# 4bitDecoder.net
KiCad netlist of a schematic drawn in Altium Designer
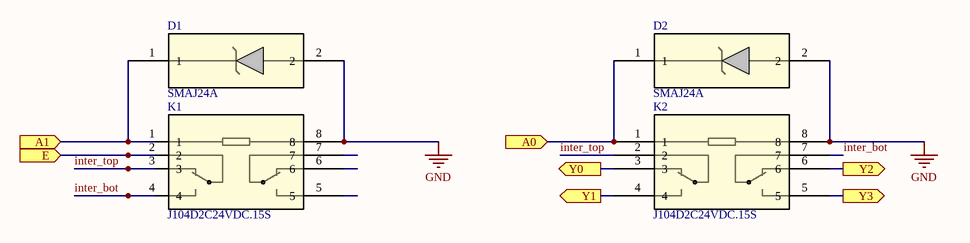
[diagram p0: 4bitDecoder.SchDoc]

(export (version "E")
  (design (tool "Eeschema 10.0.6"))
  (components
    (comp (ref "D1")
      (value "SMAJ24A")
      (footprint "DI SMAJ24A")
      (description "SMAJ Series 400 W 24 V Uni-Directional Surface Mount TVS Diode - DO-214AC")
      (fields (field (name "MANUFACTURER") "Littelfuse"))
      (libsource (lib "Schlib1") (part "DI SMAJ24A"))
    )
    (comp (ref "D2")
      (value "SMAJ24A")
      (footprint "DI SMAJ24A")
      (description "SMAJ Series 400 W 24 V Uni-Directional Surface Mount TVS Diode - DO-214AC")
      (fields (field (name "MANUFACTURER") "Littelfuse"))
      (libsource (lib "Schlib1") (part "DI SMAJ24A"))
    )
    (comp (ref "K1")
      (value "J104D2C24VDC.15S")
      (footprint "Relay J104D2C24VDC.15S")
      (description "Relay Ul Gen Purp DPDT 2C 24VDC")
      (fields (field (name "MANUFACTURER") "CIT Relay & Switch"))
      (libsource (lib "Schlib1") (part "Relay J104D2C24VDC.15S"))
    )
    (comp (ref "K2")
      (value "J104D2C24VDC.15S")
      (footprint "Relay J104D2C24VDC.15S")
      (description "Relay Ul Gen Purp DPDT 2C 24VDC")
      (fields (field (name "MANUFACTURER") "CIT Relay & Switch"))
      (libsource (lib "Schlib1") (part "Relay J104D2C24VDC.15S"))
    )
  )
  (nets
    (net (code "1") (name "/A0") (class "Default")
      (node (ref "D2") (pin "1") (pinfunction "1_1") (pintype "passive"))
      (node (ref "K2") (pin "1") (pinfunction "1_1") (pintype "passive"))
    )
    (net (code "2") (name "/A1") (class "Default")
      (node (ref "D1") (pin "1") (pinfunction "1_1") (pintype "passive"))
      (node (ref "K1") (pin "1") (pinfunction "1_1") (pintype "passive"))
    )
    (net (code "3") (name "/E") (class "Default")
      (node (ref "K1") (pin "2") (pinfunction "2_2") (pintype "passive"))
    )
    (net (code "4") (name "/Y0") (class "Default")
      (node (ref "K2") (pin "3") (pinfunction "3_3") (pintype "passive"))
    )
    (net (code "5") (name "/Y1") (class "Default")
      (node (ref "K2") (pin "4") (pinfunction "4_4") (pintype "passive"))
    )
    (net (code "6") (name "/Y2") (class "Default")
      (node (ref "K2") (pin "6") (pinfunction "6_6") (pintype "passive"))
    )
    (net (code "7") (name "/Y3") (class "Default")
      (node (ref "K2") (pin "5") (pinfunction "5_5") (pintype "passive"))
    )
    (net (code "8") (name "/inter_bot") (class "Default")
      (node (ref "K1") (pin "4") (pinfunction "4_4") (pintype "passive"))
      (node (ref "K2") (pin "7") (pinfunction "7_7") (pintype "passive"))
    )
    (net (code "9") (name "/inter_top") (class "Default")
      (node (ref "K1") (pin "3") (pinfunction "3_3") (pintype "passive"))
      (node (ref "K2") (pin "2") (pinfunction "2_2") (pintype "passive"))
    )
    (net (code "10") (name "GND") (class "Default")
      (node (ref "D1") (pin "2") (pinfunction "2_2") (pintype "passive"))
      (node (ref "D2") (pin "2") (pinfunction "2_2") (pintype "passive"))
      (node (ref "K1") (pin "8") (pinfunction "8_8") (pintype "passive"))
      (node (ref "K2") (pin "8") (pinfunction "8_8") (pintype "passive"))
    )
    (net (code "11") (name "unconnected-(K1-Pad5)") (class "Default")
      (node (ref "K1") (pin "5") (pinfunction "5_5") (pintype "passive"))
    )
    (net (code "12") (name "unconnected-(K1-Pad6)") (class "Default")
      (node (ref "K1") (pin "6") (pinfunction "6_6") (pintype "passive"))
    )
    (net (code "13") (name "unconnected-(K1-Pad7)") (class "Default")
      (node (ref "K1") (pin "7") (pinfunction "7_7") (pintype "passive"))
    )
  )
)
